# Control.net
KiCad netlist of a schematic drawn in Altium Designer
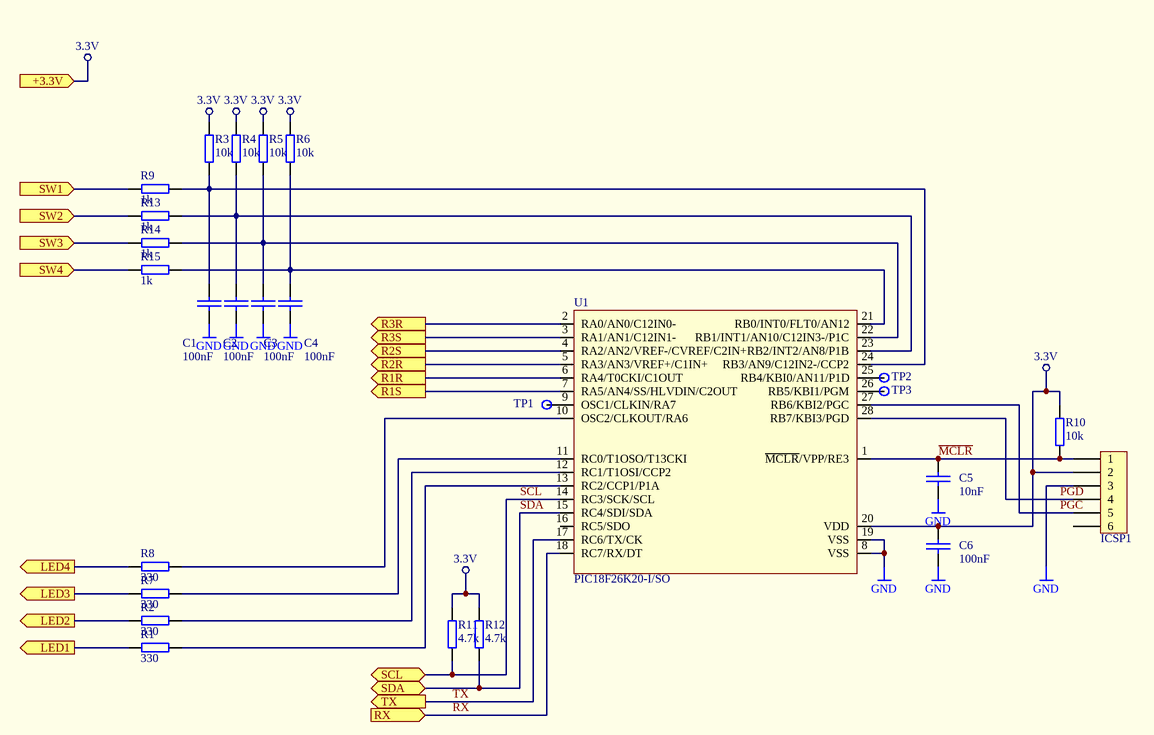
[diagram p0: Control.SchDoc]

(export (version "E")
  (design (tool "Eeschema 10.0.6"))
  (components
    (comp (ref "C1")
      (value "100nF")
      (footprint "0805_1")
      (description "Capacitor")
      (libsource (lib "MainSchlib") (part "CAP"))
    )
    (comp (ref "C2")
      (value "100nF")
      (footprint "0805_1")
      (description "Capacitor")
      (libsource (lib "MainSchlib") (part "CAP"))
    )
    (comp (ref "C3")
      (value "100nF")
      (footprint "0805_1")
      (description "Capacitor")
      (libsource (lib "MainSchlib") (part "CAP"))
    )
    (comp (ref "C4")
      (value "100nF")
      (footprint "0805_1")
      (description "Capacitor")
      (libsource (lib "MainSchlib") (part "CAP"))
    )
    (comp (ref "C5")
      (value "10nF")
      (footprint "0805_1")
      (description "Capacitor")
      (libsource (lib "*") (part "CAP"))
    )
    (comp (ref "C6")
      (value "100nF")
      (footprint "0805_1")
      (description "Capacitor")
      (libsource (lib "*") (part "CAP"))
    )
    (comp (ref "ICSP1")
      (value "CON6")
      (footprint "JP6")
      (description "Connector")
      (libsource (lib "*") (part "CON6"))
    )
    (comp (ref "R1")
      (value "330")
      (footprint "0805_1")
      (description "Resistor")
      (libsource (lib "MainSchlib") (part "RES"))
    )
    (comp (ref "R2")
      (value "330")
      (footprint "0805_1")
      (description "Resistor")
      (libsource (lib "MainSchlib") (part "RES"))
    )
    (comp (ref "R3")
      (value "10k")
      (footprint "0805_1")
      (description "Resistor")
      (libsource (lib "MainSchlib") (part "RES"))
    )
    (comp (ref "R4")
      (value "10k")
      (footprint "0805_1")
      (description "Resistor")
      (libsource (lib "MainSchlib") (part "RES"))
    )
    (comp (ref "R5")
      (value "10k")
      (footprint "0805_1")
      (description "Resistor")
      (libsource (lib "MainSchlib") (part "RES"))
    )
    (comp (ref "R6")
      (value "10k")
      (footprint "0805_1")
      (description "Resistor")
      (libsource (lib "MainSchlib") (part "RES"))
    )
    (comp (ref "R7")
      (value "330")
      (footprint "0805_1")
      (description "Resistor")
      (libsource (lib "MainSchlib") (part "RES"))
    )
    (comp (ref "R8")
      (value "330")
      (footprint "0805_1")
      (description "Resistor")
      (libsource (lib "MainSchlib") (part "RES"))
    )
    (comp (ref "R9")
      (value "1k")
      (footprint "0805_1")
      (description "Resistor")
      (libsource (lib "MainSchlib") (part "RES"))
    )
    (comp (ref "R10")
      (value "10k")
      (footprint "0805_1")
      (description "Resistor")
      (libsource (lib "*") (part "RES"))
    )
    (comp (ref "R11")
      (value "4.7k")
      (footprint "0805_1")
      (description "Resistor")
      (libsource (lib "*") (part "RES"))
    )
    (comp (ref "R12")
      (value "4.7k")
      (footprint "0805_1")
      (description "Resistor")
      (libsource (lib "*") (part "RES"))
    )
    (comp (ref "R13")
      (value "1k")
      (footprint "0805_1")
      (description "Resistor")
      (libsource (lib "MainSchlib") (part "RES"))
    )
    (comp (ref "R14")
      (value "1k")
      (footprint "0805_1")
      (description "Resistor")
      (libsource (lib "MainSchlib") (part "RES"))
    )
    (comp (ref "R15")
      (value "1k")
      (footprint "0805_1")
      (description "Resistor")
      (libsource (lib "MainSchlib") (part "RES"))
    )
    (comp (ref "TP1")
      (value "TESTPAD")
      (footprint "PAD-36/65")
      (libsource (lib "MainSchlib") (part "TESTPAD"))
    )
    (comp (ref "TP2")
      (value "TESTPAD")
      (footprint "PAD-36/65")
      (libsource (lib "MainSchlib") (part "TESTPAD"))
    )
    (comp (ref "TP3")
      (value "TESTPAD")
      (footprint "PAD-36/65")
      (libsource (lib "MainSchlib") (part "TESTPAD"))
    )
    (comp (ref "U1")
      (value "PIC18F26K20-I/SO")
      (footprint "SOIC-28")
      (description "PIC18 mid-range mcu")
      (libsource (lib "MainSchlib") (part "PIC18F26K20-I/SO"))
    )
  )
  (nets
    (net (code "1") (name "/LED1") (class "Default") (node (ref "R1") (pin "1") (pintype "passive")))
    (net (code "2") (name "/LED2") (class "Default") (node (ref "R2") (pin "1") (pintype "passive")))
    (net (code "3") (name "/LED3") (class "Default") (node (ref "R7") (pin "1") (pintype "passive")))
    (net (code "4") (name "/LED4") (class "Default") (node (ref "R8") (pin "1") (pintype "passive")))
    (net (code "5") (name "/PGC") (class "Default")
      (node (ref "ICSP1") (pin "5") (pinfunction "5_5") (pintype "passive"))
      (node (ref "U1") (pin "27") (pinfunction "RB6/KBI2/PGC_27") (pintype "passive"))
    )
    (net (code "6") (name "/PGD") (class "Default")
      (node (ref "ICSP1") (pin "4") (pinfunction "4_4") (pintype "passive"))
      (node (ref "U1") (pin "28") (pinfunction "RB7/KBI3/PGD_28") (pintype "passive"))
    )
    (net (code "7") (name "/R1R") (class "Default")
      (node (ref "U1") (pin "6") (pinfunction "RA4/T0CKI/C1OUT_6") (pintype "passive"))
    )
    (net (code "8") (name "/R1S") (class "Default")
      (node (ref "U1") (pin "7") (pinfunction "RA5/AN4/SS/HLVDIN/C2OUT_7") (pintype "passive"))
    )
    (net (code "9") (name "/R2R") (class "Default")
      (node (ref "U1") (pin "5") (pinfunction "RA3/AN3/VREF+/C1IN+_5") (pintype "passive"))
    )
    (net (code "10") (name "/R2S") (class "Default")
      (node (ref "U1") (pin "4") (pinfunction "RA2/AN2/VREF-/CVREF/C2IN+_4") (pintype "passive"))
    )
    (net (code "11") (name "/R3R") (class "Default")
      (node (ref "U1") (pin "2") (pinfunction "RA0/AN0/C12IN0-_2") (pintype "passive"))
    )
    (net (code "12") (name "/R3S") (class "Default")
      (node (ref "U1") (pin "3") (pinfunction "RA1/AN1/C12IN1-_3") (pintype "passive"))
    )
    (net (code "13") (name "/RX") (class "Default")
      (node (ref "U1") (pin "18") (pinfunction "RC7/RX/DT_18") (pintype "passive"))
    )
    (net (code "14") (name "/SCL") (class "Default")
      (node (ref "R11") (pin "1") (pintype "passive"))
      (node (ref "U1") (pin "14") (pinfunction "RC3/SCK/SCL_14") (pintype "passive"))
    )
    (net (code "15") (name "/SDA") (class "Default")
      (node (ref "R12") (pin "1") (pintype "passive"))
      (node (ref "U1") (pin "15") (pinfunction "RC4/SDI/SDA_15") (pintype "passive"))
    )
    (net (code "16") (name "/SW1") (class "Default") (node (ref "R9") (pin "2") (pintype "passive")))
    (net (code "17") (name "/SW2") (class "Default") (node (ref "R13") (pin "2") (pintype "passive")))
    (net (code "18") (name "/SW3") (class "Default") (node (ref "R14") (pin "2") (pintype "passive")))
    (net (code "19") (name "/SW4") (class "Default") (node (ref "R15") (pin "2") (pintype "passive")))
    (net (code "20") (name "/TX") (class "Default")
      (node (ref "U1") (pin "17") (pinfunction "RC6/TX/CK_17") (pintype "passive"))
    )
    (net (code "21") (name "/~{MCLR}") (class "Default")
      (node (ref "C5") (pin "1") (pinfunction "1_1") (pintype "passive"))
      (node (ref "ICSP1") (pin "1") (pinfunction "1_1") (pintype "passive"))
      (node (ref "R10") (pin "1") (pintype "passive"))
      (node (ref "U1") (pin "1") (pinfunction "~{MCLR}/VPP/RE3_1") (pintype "passive"))
    )
    (net (code "22") (name "3.3V") (class "Default")
      (node (ref "C6") (pin "1") (pinfunction "1_1") (pintype "passive"))
      (node (ref "ICSP1") (pin "2") (pinfunction "2_2") (pintype "passive"))
      (node (ref "R10") (pin "2") (pintype "passive"))
      (node (ref "R11") (pin "2") (pintype "passive"))
      (node (ref "R12") (pin "2") (pintype "passive"))
      (node (ref "R3") (pin "2") (pintype "passive"))
      (node (ref "R4") (pin "2") (pintype "passive"))
      (node (ref "R5") (pin "2") (pintype "passive"))
      (node (ref "R6") (pin "2") (pintype "passive"))
      (node (ref "U1") (pin "20") (pinfunction "VDD_20") (pintype "passive"))
    )
    (net (code "23") (name "GND") (class "Default")
      (node (ref "C1") (pin "2") (pinfunction "2_2") (pintype "passive"))
      (node (ref "C2") (pin "2") (pinfunction "2_2") (pintype "passive"))
      (node (ref "C3") (pin "2") (pinfunction "2_2") (pintype "passive"))
      (node (ref "C4") (pin "2") (pinfunction "2_2") (pintype "passive"))
      (node (ref "C5") (pin "2") (pinfunction "2_2") (pintype "passive"))
      (node (ref "C6") (pin "2") (pinfunction "2_2") (pintype "passive"))
      (node (ref "ICSP1") (pin "3") (pinfunction "3_3") (pintype "passive"))
      (node (ref "U1") (pin "19") (pinfunction "VSS_19") (pintype "passive"))
      (node (ref "U1") (pin "8") (pinfunction "VSS_8") (pintype "passive"))
    )
    (net (code "24") (name "Net-(U1-OSC1{slash}CLKIN{slash}RA7)") (class "Default")
      (node (ref "TP1") (pin "1") (pinfunction "1_1") (pintype "passive"))
      (node (ref "U1") (pin "9") (pinfunction "OSC1/CLKIN/RA7_9") (pintype "passive"))
    )
    (net (code "25") (name "Net-(U1-OSC2{slash}CLKOUT{slash}RA6)") (class "Default")
      (node (ref "R8") (pin "2") (pintype "passive"))
      (node (ref "U1") (pin "10") (pinfunction "OSC2/CLKOUT/RA6_10") (pintype "passive"))
    )
    (net (code "26") (name "Net-(U1-RB0{slash}INT0{slash}FLT0{slash}AN12)") (class "Default")
      (node (ref "C4") (pin "1") (pinfunction "1_1") (pintype "passive"))
      (node (ref "R15") (pin "1") (pintype "passive"))
      (node (ref "R6") (pin "1") (pintype "passive"))
      (node (ref "U1") (pin "21") (pinfunction "RB0/INT0/FLT0/AN12_21") (pintype "passive"))
    )
    (net (code "27") (name "Net-(U1-RB1{slash}INT1{slash}AN10{slash}C12IN3-{slash}P1C)") (class "Default")
      (node (ref "C3") (pin "1") (pinfunction "1_1") (pintype "passive"))
      (node (ref "R14") (pin "1") (pintype "passive"))
      (node (ref "R5") (pin "1") (pintype "passive"))
      (node (ref "U1") (pin "22") (pinfunction "RB1/INT1/AN10/C12IN3-/P1C_22") (pintype "passive"))
    )
    (net (code "28") (name "Net-(U1-RB2{slash}INT2{slash}AN8{slash}P1B)") (class "Default")
      (node (ref "C2") (pin "1") (pinfunction "1_1") (pintype "passive"))
      (node (ref "R13") (pin "1") (pintype "passive"))
      (node (ref "R4") (pin "1") (pintype "passive"))
      (node (ref "U1") (pin "23") (pinfunction "RB2/INT2/AN8/P1B_23") (pintype "passive"))
    )
    (net (code "29") (name "Net-(U1-RB3{slash}AN9{slash}C12IN2-{slash}CCP2)") (class "Default")
      (node (ref "C1") (pin "1") (pinfunction "1_1") (pintype "passive"))
      (node (ref "R3") (pin "1") (pintype "passive"))
      (node (ref "R9") (pin "1") (pintype "passive"))
      (node (ref "U1") (pin "24") (pinfunction "RB3/AN9/C12IN2-/CCP2_24") (pintype "passive"))
    )
    (net (code "30") (name "Net-(U1-RB4{slash}KBI0{slash}AN11{slash}P1D)") (class "Default")
      (node (ref "TP2") (pin "1") (pinfunction "1_1") (pintype "passive"))
      (node (ref "U1") (pin "25") (pinfunction "RB4/KBI0/AN11/P1D_25") (pintype "passive"))
    )
    (net (code "31") (name "Net-(U1-RB5{slash}KBI1{slash}PGM)") (class "Default")
      (node (ref "TP3") (pin "1") (pinfunction "1_1") (pintype "passive"))
      (node (ref "U1") (pin "26") (pinfunction "RB5/KBI1/PGM_26") (pintype "passive"))
    )
    (net (code "32") (name "Net-(U1-RC0{slash}T1OSO{slash}T13CKI)") (class "Default")
      (node (ref "R7") (pin "2") (pintype "passive"))
      (node (ref "U1") (pin "11") (pinfunction "RC0/T1OSO/T13CKI_11") (pintype "passive"))
    )
    (net (code "33") (name "Net-(U1-RC1{slash}T1OSI{slash}CCP2)") (class "Default")
      (node (ref "R2") (pin "2") (pintype "passive"))
      (node (ref "U1") (pin "12") (pinfunction "RC1/T1OSI/CCP2_12") (pintype "passive"))
    )
    (net (code "34") (name "Net-(U1-RC2{slash}CCP1{slash}P1A)") (class "Default")
      (node (ref "R1") (pin "2") (pintype "passive"))
      (node (ref "U1") (pin "13") (pinfunction "RC2/CCP1/P1A_13") (pintype "passive"))
    )
    (net (code "35") (name "unconnected-(ICSP1-Pad6)") (class "Default")
      (node (ref "ICSP1") (pin "6") (pinfunction "6_6") (pintype "passive"))
    )
    (net (code "36") (name "unconnected-(U1-RC5{slash}SDO-Pad16)") (class "Default")
      (node (ref "U1") (pin "16") (pinfunction "RC5/SDO_16") (pintype "passive"))
    )
  )
)
